# AUDIO_005.net
KiCad netlist of a schematic drawn in EAGLE
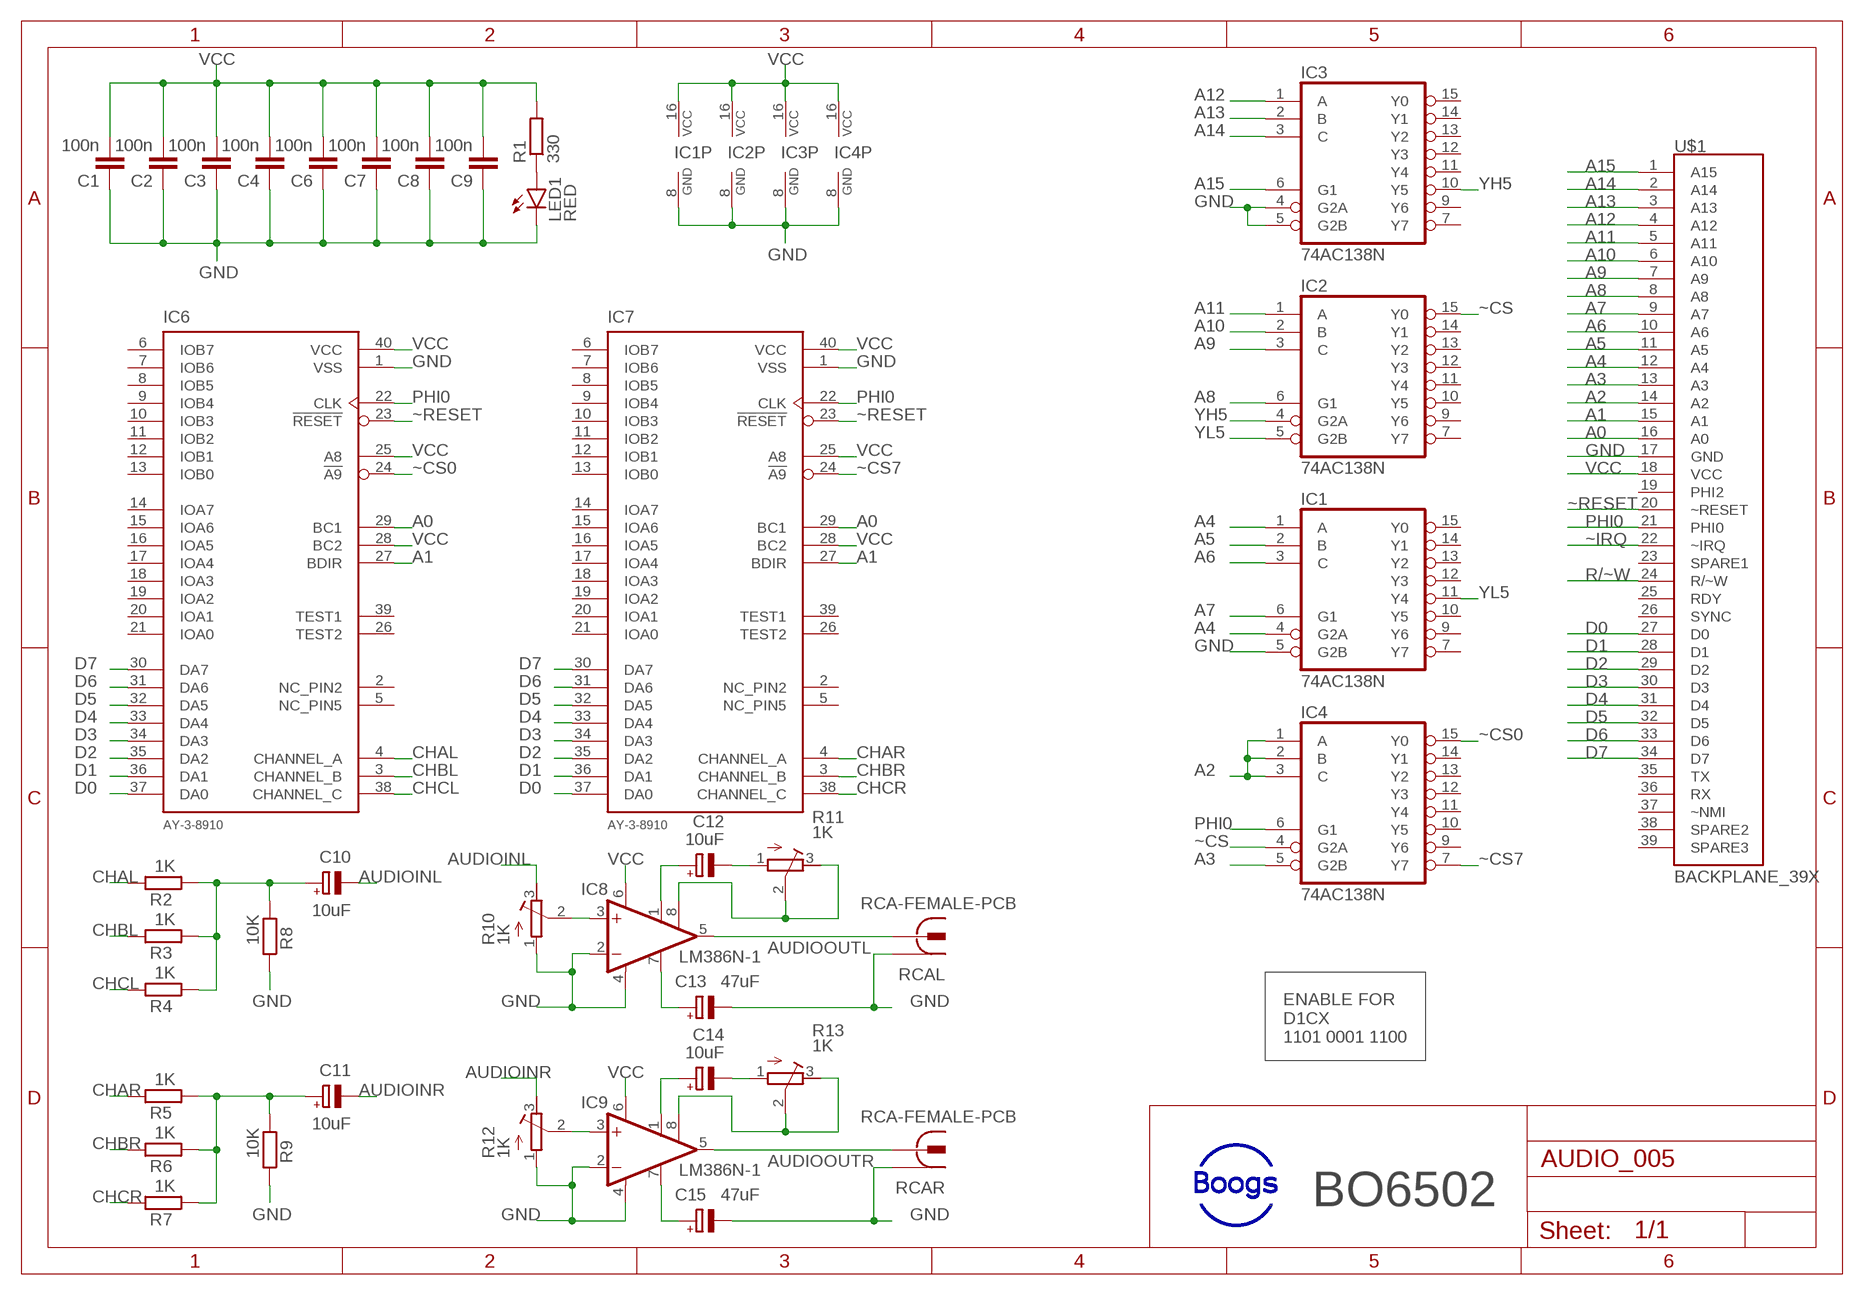
[diagram p0: schematic, sheet 1]

(export (version "E")
  (design (tool "Eeschema 10.0.6"))
  (components
    (comp (ref "C1")
      (value "100n")
      (footprint "eagle-import:C025-025X050")
      (libsource (lib "eagle-import") (part "C-EU025-025X050"))
    )
    (comp (ref "C2")
      (value "100n")
      (footprint "eagle-import:C025-025X050")
      (libsource (lib "eagle-import") (part "C-EU025-025X050"))
    )
    (comp (ref "C3")
      (value "100n")
      (footprint "eagle-import:C025-025X050")
      (libsource (lib "eagle-import") (part "C-EU025-025X050"))
    )
    (comp (ref "C4")
      (value "100n")
      (footprint "eagle-import:C025-025X050")
      (libsource (lib "eagle-import") (part "C-EU025-025X050"))
    )
    (comp (ref "C6")
      (value "100n")
      (footprint "eagle-import:C025-025X050")
      (libsource (lib "eagle-import") (part "C-EU025-025X050"))
    )
    (comp (ref "C7")
      (value "100n")
      (footprint "eagle-import:C025-025X050")
      (libsource (lib "eagle-import") (part "C-EU025-025X050"))
    )
    (comp (ref "C8")
      (value "100n")
      (footprint "eagle-import:C025-025X050")
      (libsource (lib "eagle-import") (part "C-EU025-025X050"))
    )
    (comp (ref "C9")
      (value "100n")
      (footprint "eagle-import:C025-025X050")
      (libsource (lib "eagle-import") (part "C-EU025-025X050"))
    )
    (comp (ref "C10")
      (value "10uF")
      (footprint "eagle-import:B45181A")
      (libsource (lib "eagle-import") (part "CPOL-EUB45181A"))
    )
    (comp (ref "C11")
      (value "10uF")
      (footprint "eagle-import:B45181A")
      (libsource (lib "eagle-import") (part "CPOL-EUB45181A"))
    )
    (comp (ref "C12")
      (value "10uF")
      (footprint "eagle-import:B45181A")
      (libsource (lib "eagle-import") (part "CPOL-EUB45181A"))
    )
    (comp (ref "C13")
      (value "47uF")
      (footprint "eagle-import:B45181A")
      (libsource (lib "eagle-import") (part "CPOL-EUB45181A"))
    )
    (comp (ref "C14")
      (value "10uF")
      (footprint "eagle-import:B45181A")
      (libsource (lib "eagle-import") (part "CPOL-EUB45181A"))
    )
    (comp (ref "C15")
      (value "47uF")
      (footprint "eagle-import:B45181A")
      (libsource (lib "eagle-import") (part "CPOL-EUB45181A"))
    )
    (comp (ref "IC1")
      (value "74AC138N")
      (footprint "eagle-import:DIL16")
      (libsource (lib "eagle-import") (part "74138NAC"))
    )
    (comp (ref "IC2")
      (value "74AC138N")
      (footprint "eagle-import:DIL16")
      (libsource (lib "eagle-import") (part "74138NAC"))
    )
    (comp (ref "IC3")
      (value "74AC138N")
      (footprint "eagle-import:DIL16")
      (libsource (lib "eagle-import") (part "74138NAC"))
    )
    (comp (ref "IC4")
      (value "74AC138N")
      (footprint "eagle-import:DIL16")
      (libsource (lib "eagle-import") (part "74138NAC"))
    )
    (comp (ref "IC6")
      (value "AY-3-8910")
      (footprint "eagle-import:DIL40")
      (fields (field (name "MF") "General Instrument"))
      (libsource (lib "eagle-import") (part "AY-3-8910"))
    )
    (comp (ref "IC7")
      (value "AY-3-8910")
      (footprint "eagle-import:DIL40")
      (fields (field (name "MF") "General Instrument"))
      (libsource (lib "eagle-import") (part "AY-3-8910"))
    )
    (comp (ref "IC8")
      (value "LM386N-1")
      (footprint "eagle-import:DIL08")
      (libsource (lib "eagle-import") (part "LM386?-N1"))
    )
    (comp (ref "IC9")
      (value "LM386N-1")
      (footprint "eagle-import:DIL08")
      (libsource (lib "eagle-import") (part "LM386?-N1"))
    )
    (comp (ref "LED1")
      (value "RED")
      (footprint "eagle-import:LED5MM")
      (libsource (lib "eagle-import") (part "LED5MM"))
    )
    (comp (ref "R1")
      (value "330")
      (footprint "eagle-import:0207_10")
      (libsource (lib "eagle-import") (part "R-EU_0207/10"))
    )
    (comp (ref "R2")
      (value "1K")
      (footprint "eagle-import:0207_10")
      (libsource (lib "eagle-import") (part "R-EU_0207/10"))
    )
    (comp (ref "R3")
      (value "1K")
      (footprint "eagle-import:0207_10")
      (libsource (lib "eagle-import") (part "R-EU_0207/10"))
    )
    (comp (ref "R4")
      (value "1K")
      (footprint "eagle-import:0207_10")
      (libsource (lib "eagle-import") (part "R-EU_0207/10"))
    )
    (comp (ref "R5")
      (value "1K")
      (footprint "eagle-import:0207_10")
      (libsource (lib "eagle-import") (part "R-EU_0207/10"))
    )
    (comp (ref "R6")
      (value "1K")
      (footprint "eagle-import:0207_10")
      (libsource (lib "eagle-import") (part "R-EU_0207/10"))
    )
    (comp (ref "R7")
      (value "1K")
      (footprint "eagle-import:0207_10")
      (libsource (lib "eagle-import") (part "R-EU_0207/10"))
    )
    (comp (ref "R8")
      (value "10K")
      (footprint "eagle-import:0207_10")
      (libsource (lib "eagle-import") (part "R-EU_0207/10"))
    )
    (comp (ref "R9")
      (value "10K")
      (footprint "eagle-import:0207_10")
      (libsource (lib "eagle-import") (part "R-EU_0207/10"))
    )
    (comp (ref "R10")
      (value "1K")
      (footprint "eagle-import:RTRIM3339P")
      (libsource (lib "eagle-import") (part "R-TRIMM3339P"))
    )
    (comp (ref "R11")
      (value "1K")
      (footprint "eagle-import:RTRIM3339P")
      (libsource (lib "eagle-import") (part "R-TRIMM3339P"))
    )
    (comp (ref "R12")
      (value "1K")
      (footprint "eagle-import:RTRIM3339P")
      (libsource (lib "eagle-import") (part "R-TRIMM3339P"))
    )
    (comp (ref "R13")
      (value "1K")
      (footprint "eagle-import:RTRIM3339P")
      (libsource (lib "eagle-import") (part "R-TRIMM3339P"))
    )
    (comp (ref "RCAL")
      (value "RCA-FEMALE-PCB")
      (footprint "eagle-import:RCA-FEMALE-PCB")
      (libsource (lib "eagle-import") (part "RCA-FEMALE-PCB"))
    )
    (comp (ref "RCAR")
      (value "RCA-FEMALE-PCB")
      (footprint "eagle-import:RCA-FEMALE-PCB")
      (libsource (lib "eagle-import") (part "RCA-FEMALE-PCB"))
    )
    (comp (ref "U$1")
      (value "BACKPLANE_39X")
      (footprint "eagle-import:BP_39X")
      (libsource (lib "eagle-import") (part "BACKPLANE_39X"))
    )
  )
  (nets
    (net (code "1") (name "/A0") (class "Default")
      (node (ref "IC6") (pin "29") (pinfunction "BC1_29") (pintype "input"))
      (node (ref "IC7") (pin "29") (pinfunction "BC1_29") (pintype "input"))
      (node (ref "U$1") (pin "16") (pinfunction "A0_16") (pintype "bidirectional"))
    )
    (net (code "2") (name "/A1") (class "Default")
      (node (ref "IC6") (pin "27") (pinfunction "BDIR_27") (pintype "input"))
      (node (ref "IC7") (pin "27") (pinfunction "BDIR_27") (pintype "input"))
      (node (ref "U$1") (pin "15") (pinfunction "A1_15") (pintype "bidirectional"))
    )
    (net (code "3") (name "/A2") (class "Default")
      (node (ref "IC4") (pin "1") (pinfunction "A_1") (pintype "input"))
      (node (ref "IC4") (pin "2") (pinfunction "B_2") (pintype "input"))
      (node (ref "IC4") (pin "3") (pinfunction "C_3") (pintype "input"))
      (node (ref "U$1") (pin "14") (pinfunction "A2_14") (pintype "bidirectional"))
    )
    (net (code "4") (name "/A3") (class "Default")
      (node (ref "IC4") (pin "5") (pinfunction "G2B_5") (pintype "input"))
      (node (ref "U$1") (pin "13") (pinfunction "A3_13") (pintype "bidirectional"))
    )
    (net (code "5") (name "/A4") (class "Default")
      (node (ref "IC1") (pin "1") (pinfunction "A_1") (pintype "input"))
      (node (ref "IC1") (pin "4") (pinfunction "G2A_4") (pintype "input"))
      (node (ref "U$1") (pin "12") (pinfunction "A4_12") (pintype "bidirectional"))
    )
    (net (code "6") (name "/A5") (class "Default")
      (node (ref "IC1") (pin "2") (pinfunction "B_2") (pintype "input"))
      (node (ref "U$1") (pin "11") (pinfunction "A5_11") (pintype "bidirectional"))
    )
    (net (code "7") (name "/A6") (class "Default")
      (node (ref "IC1") (pin "3") (pinfunction "C_3") (pintype "input"))
      (node (ref "U$1") (pin "10") (pinfunction "A6_10") (pintype "bidirectional"))
    )
    (net (code "8") (name "/A7") (class "Default")
      (node (ref "IC1") (pin "6") (pinfunction "G1_6") (pintype "input"))
      (node (ref "U$1") (pin "9") (pinfunction "A7_9") (pintype "bidirectional"))
    )
    (net (code "9") (name "/A8") (class "Default")
      (node (ref "IC2") (pin "6") (pinfunction "G1_6") (pintype "input"))
      (node (ref "U$1") (pin "8") (pinfunction "A8_8") (pintype "bidirectional"))
    )
    (net (code "10") (name "/A9") (class "Default")
      (node (ref "IC2") (pin "3") (pinfunction "C_3") (pintype "input"))
      (node (ref "U$1") (pin "7") (pinfunction "A9_7") (pintype "bidirectional"))
    )
    (net (code "11") (name "/A10") (class "Default")
      (node (ref "IC2") (pin "2") (pinfunction "B_2") (pintype "input"))
      (node (ref "U$1") (pin "6") (pinfunction "A10_6") (pintype "bidirectional"))
    )
    (net (code "12") (name "/A11") (class "Default")
      (node (ref "IC2") (pin "1") (pinfunction "A_1") (pintype "input"))
      (node (ref "U$1") (pin "5") (pinfunction "A11_5") (pintype "bidirectional"))
    )
    (net (code "13") (name "/A12") (class "Default")
      (node (ref "IC3") (pin "1") (pinfunction "A_1") (pintype "input"))
      (node (ref "U$1") (pin "4") (pinfunction "A12_4") (pintype "bidirectional"))
    )
    (net (code "14") (name "/A13") (class "Default")
      (node (ref "IC3") (pin "2") (pinfunction "B_2") (pintype "input"))
      (node (ref "U$1") (pin "3") (pinfunction "A13_3") (pintype "bidirectional"))
    )
    (net (code "15") (name "/A14") (class "Default")
      (node (ref "IC3") (pin "3") (pinfunction "C_3") (pintype "input"))
      (node (ref "U$1") (pin "2") (pinfunction "A14_2") (pintype "bidirectional"))
    )
    (net (code "16") (name "/A15") (class "Default")
      (node (ref "IC3") (pin "6") (pinfunction "G1_6") (pintype "input"))
      (node (ref "U$1") (pin "1") (pinfunction "A15_1") (pintype "bidirectional"))
    )
    (net (code "17") (name "/AUDIOINL") (class "Default")
      (node (ref "C10") (pin "-") (pinfunction "-_-") (pintype "passive"))
      (node (ref "R10") (pin "3") (pinfunction "E_3") (pintype "passive"))
    )
    (net (code "18") (name "/AUDIOINR") (class "Default")
      (node (ref "C11") (pin "-") (pinfunction "-_-") (pintype "passive"))
      (node (ref "R12") (pin "3") (pinfunction "E_3") (pintype "passive"))
    )
    (net (code "19") (name "/AUDIOOUTL") (class "Default")
      (node (ref "IC8") (pin "5") (pinfunction "OUT_5") (pintype "output"))
      (node (ref "RCAL") (pin "2@1") (pinfunction "2_2@1") (pintype "passive"))
      (node (ref "RCAL") (pin "2@2") (pinfunction "2_2@2") (pintype "passive"))
    )
    (net (code "20") (name "/AUDIOOUTR") (class "Default")
      (node (ref "IC9") (pin "5") (pinfunction "OUT_5") (pintype "output"))
      (node (ref "RCAR") (pin "2@1") (pinfunction "2_2@1") (pintype "passive"))
      (node (ref "RCAR") (pin "2@2") (pinfunction "2_2@2") (pintype "passive"))
    )
    (net (code "21") (name "/CHAL") (class "Default")
      (node (ref "IC6") (pin "4") (pinfunction "CHANNEL_A_4") (pintype "output"))
      (node (ref "R2") (pin "1") (pinfunction "1_1") (pintype "passive"))
    )
    (net (code "22") (name "/CHAR") (class "Default")
      (node (ref "IC7") (pin "4") (pinfunction "CHANNEL_A_4") (pintype "output"))
      (node (ref "R5") (pin "1") (pinfunction "1_1") (pintype "passive"))
    )
    (net (code "23") (name "/CHBL") (class "Default")
      (node (ref "IC6") (pin "3") (pinfunction "CHANNEL_B_3") (pintype "output"))
      (node (ref "R3") (pin "1") (pinfunction "1_1") (pintype "passive"))
    )
    (net (code "24") (name "/CHBR") (class "Default")
      (node (ref "IC7") (pin "3") (pinfunction "CHANNEL_B_3") (pintype "output"))
      (node (ref "R6") (pin "1") (pinfunction "1_1") (pintype "passive"))
    )
    (net (code "25") (name "/CHCL") (class "Default")
      (node (ref "IC6") (pin "38") (pinfunction "CHANNEL_C_38") (pintype "output"))
      (node (ref "R4") (pin "1") (pinfunction "1_1") (pintype "passive"))
    )
    (net (code "26") (name "/CHCR") (class "Default")
      (node (ref "IC7") (pin "38") (pinfunction "CHANNEL_C_38") (pintype "output"))
      (node (ref "R7") (pin "1") (pinfunction "1_1") (pintype "passive"))
    )
    (net (code "27") (name "/D0") (class "Default")
      (node (ref "IC6") (pin "37") (pinfunction "DA0_37") (pintype "bidirectional"))
      (node (ref "IC7") (pin "37") (pinfunction "DA0_37") (pintype "bidirectional"))
      (node (ref "U$1") (pin "27") (pinfunction "D0_27") (pintype "bidirectional"))
    )
    (net (code "28") (name "/D1") (class "Default")
      (node (ref "IC6") (pin "36") (pinfunction "DA1_36") (pintype "bidirectional"))
      (node (ref "IC7") (pin "36") (pinfunction "DA1_36") (pintype "bidirectional"))
      (node (ref "U$1") (pin "28") (pinfunction "D1_28") (pintype "bidirectional"))
    )
    (net (code "29") (name "/D2") (class "Default")
      (node (ref "IC6") (pin "35") (pinfunction "DA2_35") (pintype "bidirectional"))
      (node (ref "IC7") (pin "35") (pinfunction "DA2_35") (pintype "bidirectional"))
      (node (ref "U$1") (pin "29") (pinfunction "D2_29") (pintype "bidirectional"))
    )
    (net (code "30") (name "/D3") (class "Default")
      (node (ref "IC6") (pin "34") (pinfunction "DA3_34") (pintype "bidirectional"))
      (node (ref "IC7") (pin "34") (pinfunction "DA3_34") (pintype "bidirectional"))
      (node (ref "U$1") (pin "30") (pinfunction "D3_30") (pintype "bidirectional"))
    )
    (net (code "31") (name "/D4") (class "Default")
      (node (ref "IC6") (pin "33") (pinfunction "DA4_33") (pintype "bidirectional"))
      (node (ref "IC7") (pin "33") (pinfunction "DA4_33") (pintype "bidirectional"))
      (node (ref "U$1") (pin "31") (pinfunction "D4_31") (pintype "bidirectional"))
    )
    (net (code "32") (name "/D5") (class "Default")
      (node (ref "IC6") (pin "32") (pinfunction "DA5_32") (pintype "bidirectional"))
      (node (ref "IC7") (pin "32") (pinfunction "DA5_32") (pintype "bidirectional"))
      (node (ref "U$1") (pin "32") (pinfunction "D5_32") (pintype "bidirectional"))
    )
    (net (code "33") (name "/D6") (class "Default")
      (node (ref "IC6") (pin "31") (pinfunction "DA6_31") (pintype "bidirectional"))
      (node (ref "IC7") (pin "31") (pinfunction "DA6_31") (pintype "bidirectional"))
      (node (ref "U$1") (pin "33") (pinfunction "D6_33") (pintype "bidirectional"))
    )
    (net (code "34") (name "/D7") (class "Default")
      (node (ref "IC6") (pin "30") (pinfunction "DA7_30") (pintype "bidirectional"))
      (node (ref "IC7") (pin "30") (pinfunction "DA7_30") (pintype "bidirectional"))
      (node (ref "U$1") (pin "34") (pinfunction "D7_34") (pintype "bidirectional"))
    )
    (net (code "35") (name "/GND") (class "Default")
      (node (ref "C1") (pin "1") (pinfunction "1_1") (pintype "passive"))
      (node (ref "C13") (pin "-") (pinfunction "-_-") (pintype "passive"))
      (node (ref "C15") (pin "-") (pinfunction "-_-") (pintype "passive"))
      (node (ref "C2") (pin "1") (pinfunction "1_1") (pintype "passive"))
      (node (ref "C3") (pin "1") (pinfunction "1_1") (pintype "passive"))
      (node (ref "C4") (pin "1") (pinfunction "1_1") (pintype "passive"))
      (node (ref "C6") (pin "1") (pinfunction "1_1") (pintype "passive"))
      (node (ref "C7") (pin "1") (pinfunction "1_1") (pintype "passive"))
      (node (ref "C8") (pin "1") (pinfunction "1_1") (pintype "passive"))
      (node (ref "C9") (pin "1") (pinfunction "1_1") (pintype "passive"))
      (node (ref "IC1") (pin "5") (pinfunction "G2B_5") (pintype "input"))
      (node (ref "IC1") (pin "8") (pinfunction "GND_8") (pintype "power_in"))
      (node (ref "IC2") (pin "8") (pinfunction "GND_8") (pintype "power_in"))
      (node (ref "IC3") (pin "4") (pinfunction "G2A_4") (pintype "input"))
      (node (ref "IC3") (pin "5") (pinfunction "G2B_5") (pintype "input"))
      (node (ref "IC3") (pin "8") (pinfunction "GND_8") (pintype "power_in"))
      (node (ref "IC4") (pin "8") (pinfunction "GND_8") (pintype "power_in"))
      (node (ref "IC6") (pin "1") (pinfunction "VSS_1") (pintype "power_in"))
      (node (ref "IC7") (pin "1") (pinfunction "VSS_1") (pintype "power_in"))
      (node (ref "IC8") (pin "2") (pinfunction "-IN_2") (pintype "input"))
      (node (ref "IC8") (pin "4") (pinfunction "GND_4") (pintype "power_in"))
      (node (ref "IC9") (pin "2") (pinfunction "-IN_2") (pintype "input"))
      (node (ref "IC9") (pin "4") (pinfunction "GND_4") (pintype "power_in"))
      (node (ref "LED1") (pin "K") (pinfunction "C_K") (pintype "passive"))
      (node (ref "R10") (pin "1") (pinfunction "A_1") (pintype "passive"))
      (node (ref "R12") (pin "1") (pinfunction "A_1") (pintype "passive"))
      (node (ref "R8") (pin "1") (pinfunction "1_1") (pintype "passive"))
      (node (ref "R9") (pin "1") (pinfunction "1_1") (pintype "passive"))
      (node (ref "RCAL") (pin "1") (pinfunction "1_1") (pintype "passive"))
      (node (ref "RCAR") (pin "1") (pinfunction "1_1") (pintype "passive"))
      (node (ref "U$1") (pin "17") (pinfunction "GND_17") (pintype "bidirectional"))
    )
    (net (code "36") (name "/PHI0") (class "Default")
      (node (ref "IC4") (pin "6") (pinfunction "G1_6") (pintype "input"))
      (node (ref "IC6") (pin "22") (pinfunction "CLK_22") (pintype "input"))
      (node (ref "IC7") (pin "22") (pinfunction "CLK_22") (pintype "input"))
      (node (ref "U$1") (pin "21") (pinfunction "PHI0_21") (pintype "bidirectional"))
    )
    (net (code "37") (name "/R{slash}~{W}") (class "Default")
      (node (ref "U$1") (pin "24") (pinfunction "R/~{W}_24") (pintype "bidirectional"))
    )
    (net (code "38") (name "/VCC") (class "Default")
      (node (ref "C1") (pin "2") (pinfunction "2_2") (pintype "passive"))
      (node (ref "C2") (pin "2") (pinfunction "2_2") (pintype "passive"))
      (node (ref "C3") (pin "2") (pinfunction "2_2") (pintype "passive"))
      (node (ref "C4") (pin "2") (pinfunction "2_2") (pintype "passive"))
      (node (ref "C6") (pin "2") (pinfunction "2_2") (pintype "passive"))
      (node (ref "C7") (pin "2") (pinfunction "2_2") (pintype "passive"))
      (node (ref "C8") (pin "2") (pinfunction "2_2") (pintype "passive"))
      (node (ref "C9") (pin "2") (pinfunction "2_2") (pintype "passive"))
      (node (ref "IC1") (pin "16") (pinfunction "VCC_16") (pintype "power_in"))
      (node (ref "IC2") (pin "16") (pinfunction "VCC_16") (pintype "power_in"))
      (node (ref "IC3") (pin "16") (pinfunction "VCC_16") (pintype "power_in"))
      (node (ref "IC4") (pin "16") (pinfunction "VCC_16") (pintype "power_in"))
      (node (ref "IC6") (pin "25") (pinfunction "A8_25") (pintype "bidirectional"))
      (node (ref "IC6") (pin "28") (pinfunction "BC2_28") (pintype "input"))
      (node (ref "IC6") (pin "40") (pinfunction "VCC_40") (pintype "power_in"))
      (node (ref "IC7") (pin "25") (pinfunction "A8_25") (pintype "bidirectional"))
      (node (ref "IC7") (pin "28") (pinfunction "BC2_28") (pintype "input"))
      (node (ref "IC7") (pin "40") (pinfunction "VCC_40") (pintype "power_in"))
      (node (ref "IC8") (pin "6") (pinfunction "VS_6") (pintype "power_in"))
      (node (ref "IC9") (pin "6") (pinfunction "VS_6") (pintype "power_in"))
      (node (ref "R1") (pin "2") (pinfunction "2_2") (pintype "passive"))
      (node (ref "U$1") (pin "18") (pinfunction "VCC_18") (pintype "bidirectional"))
    )
    (net (code "39") (name "/YH5") (class "Default")
      (node (ref "IC2") (pin "4") (pinfunction "G2A_4") (pintype "input"))
      (node (ref "IC3") (pin "10") (pinfunction "Y5_10") (pintype "output"))
    )
    (net (code "40") (name "/YL5") (class "Default")
      (node (ref "IC1") (pin "11") (pinfunction "Y4_11") (pintype "output"))
      (node (ref "IC2") (pin "5") (pinfunction "G2B_5") (pintype "input"))
    )
    (net (code "41") (name "/~{CS0}") (class "Default")
      (node (ref "IC4") (pin "15") (pinfunction "Y0_15") (pintype "output"))
      (node (ref "IC6") (pin "24") (pinfunction "~{A9}_24") (pintype "bidirectional"))
    )
    (net (code "42") (name "/~{CS7}") (class "Default")
      (node (ref "IC4") (pin "7") (pinfunction "Y7_7") (pintype "output"))
      (node (ref "IC7") (pin "24") (pinfunction "~{A9}_24") (pintype "bidirectional"))
    )
    (net (code "43") (name "/~{CS}") (class "Default")
      (node (ref "IC2") (pin "15") (pinfunction "Y0_15") (pintype "output"))
      (node (ref "IC4") (pin "4") (pinfunction "G2A_4") (pintype "input"))
    )
    (net (code "44") (name "/~{IRQ}") (class "Default")
      (node (ref "U$1") (pin "22") (pinfunction "~{IRQ}_22") (pintype "bidirectional"))
    )
    (net (code "45") (name "/~{RESET}") (class "Default")
      (node (ref "IC6") (pin "23") (pinfunction "~{RESET}_23") (pintype "input"))
      (node (ref "IC7") (pin "23") (pinfunction "~{RESET}_23") (pintype "input"))
      (node (ref "U$1") (pin "20") (pinfunction "~{RESET}_20") (pintype "bidirectional"))
    )
    (net (code "46") (name "Net-(C10-Pad+)") (class "Default")
      (node (ref "C10") (pin "+") (pinfunction "+_+") (pintype "passive"))
      (node (ref "R2") (pin "2") (pinfunction "2_2") (pintype "passive"))
      (node (ref "R3") (pin "2") (pinfunction "2_2") (pintype "passive"))
      (node (ref "R4") (pin "2") (pinfunction "2_2") (pintype "passive"))
      (node (ref "R8") (pin "2") (pinfunction "2_2") (pintype "passive"))
    )
    (net (code "47") (name "Net-(C11-Pad+)") (class "Default")
      (node (ref "C11") (pin "+") (pinfunction "+_+") (pintype "passive"))
      (node (ref "R5") (pin "2") (pinfunction "2_2") (pintype "passive"))
      (node (ref "R6") (pin "2") (pinfunction "2_2") (pintype "passive"))
      (node (ref "R7") (pin "2") (pinfunction "2_2") (pintype "passive"))
      (node (ref "R9") (pin "2") (pinfunction "2_2") (pintype "passive"))
    )
    (net (code "48") (name "Net-(C12-Pad+)") (class "Default")
      (node (ref "C12") (pin "+") (pinfunction "+_+") (pintype "passive"))
      (node (ref "IC8") (pin "1") (pinfunction "GAIN_1") (pintype "passive"))
    )
    (net (code "49") (name "Net-(C14-Pad+)") (class "Default")
      (node (ref "C14") (pin "+") (pinfunction "+_+") (pintype "passive"))
      (node (ref "IC9") (pin "1") (pinfunction "GAIN_1") (pintype "passive"))
    )
    (net (code "50") (name "Net-(IC8-+IN)") (class "Default")
      (node (ref "IC8") (pin "3") (pinfunction "+IN_3") (pintype "input"))
      (node (ref "R10") (pin "2") (pinfunction "S_2") (pintype "passive"))
    )
    (net (code "51") (name "Net-(IC8-BYPASS)") (class "Default")
      (node (ref "C13") (pin "+") (pinfunction "+_+") (pintype "passive"))
      (node (ref "IC8") (pin "7") (pinfunction "BYPASS_7") (pintype "passive"))
    )
    (net (code "52") (name "Net-(IC9-+IN)") (class "Default")
      (node (ref "IC9") (pin "3") (pinfunction "+IN_3") (pintype "input"))
      (node (ref "R12") (pin "2") (pinfunction "S_2") (pintype "passive"))
    )
    (net (code "53") (name "Net-(IC9-BYPASS)") (class "Default")
      (node (ref "C15") (pin "+") (pinfunction "+_+") (pintype "passive"))
      (node (ref "IC9") (pin "7") (pinfunction "BYPASS_7") (pintype "passive"))
    )
    (net (code "54") (name "Net-(LED1-PadA)") (class "Default")
      (node (ref "LED1") (pin "A") (pinfunction "A_A") (pintype "passive"))
      (node (ref "R1") (pin "1") (pinfunction "1_1") (pintype "passive"))
    )
    (net (code "55") (name "Net-(R11-A)") (class "Default")
      (node (ref "C12") (pin "-") (pinfunction "-_-") (pintype "passive"))
      (node (ref "R11") (pin "1") (pinfunction "A_1") (pintype "passive"))
    )
    (net (code "56") (name "Net-(R11-E)") (class "Default")
      (node (ref "IC8") (pin "8") (pinfunction "GAIN_8") (pintype "passive"))
      (node (ref "R11") (pin "2") (pinfunction "S_2") (pintype "passive"))
      (node (ref "R11") (pin "3") (pinfunction "E_3") (pintype "passive"))
    )
    (net (code "57") (name "Net-(R13-A)") (class "Default")
      (node (ref "C14") (pin "-") (pinfunction "-_-") (pintype "passive"))
      (node (ref "R13") (pin "1") (pinfunction "A_1") (pintype "passive"))
    )
    (net (code "58") (name "Net-(R13-E)") (class "Default")
      (node (ref "IC9") (pin "8") (pinfunction "GAIN_8") (pintype "passive"))
      (node (ref "R13") (pin "2") (pinfunction "S_2") (pintype "passive"))
      (node (ref "R13") (pin "3") (pinfunction "E_3") (pintype "passive"))
    )
    (net (code "59") (name "unconnected-(IC1A-Y0-Pad15)") (class "Default")
      (node (ref "IC1") (pin "15") (pinfunction "Y0_15") (pintype "output"))
    )
    (net (code "60") (name "unconnected-(IC1A-Y1-Pad14)") (class "Default")
      (node (ref "IC1") (pin "14") (pinfunction "Y1_14") (pintype "output"))
    )
    (net (code "61") (name "unconnected-(IC1A-Y2-Pad13)") (class "Default")
      (node (ref "IC1") (pin "13") (pinfunction "Y2_13") (pintype "output"))
    )
    (net (code "62") (name "unconnected-(IC1A-Y3-Pad12)") (class "Default")
      (node (ref "IC1") (pin "12") (pinfunction "Y3_12") (pintype "output"))
    )
    (net (code "63") (name "unconnected-(IC1A-Y5-Pad10)") (class "Default")
      (node (ref "IC1") (pin "10") (pinfunction "Y5_10") (pintype "output"))
    )
    (net (code "64") (name "unconnected-(IC1A-Y6-Pad9)") (class "Default")
      (node (ref "IC1") (pin "9") (pinfunction "Y6_9") (pintype "output"))
    )
    (net (code "65") (name "unconnected-(IC1A-Y7-Pad7)") (class "Default")
      (node (ref "IC1") (pin "7") (pinfunction "Y7_7") (pintype "output"))
    )
    (net (code "66") (name "unconnected-(IC2A-Y1-Pad14)") (class "Default")
      (node (ref "IC2") (pin "14") (pinfunction "Y1_14") (pintype "output"))
    )
    (net (code "67") (name "unconnected-(IC2A-Y2-Pad13)") (class "Default")
      (node (ref "IC2") (pin "13") (pinfunction "Y2_13") (pintype "output"))
    )
    (net (code "68") (name "unconnected-(IC2A-Y3-Pad12)") (class "Default")
      (node (ref "IC2") (pin "12") (pinfunction "Y3_12") (pintype "output"))
    )
    (net (code "69") (name "unconnected-(IC2A-Y4-Pad11)") (class "Default")
      (node (ref "IC2") (pin "11") (pinfunction "Y4_11") (pintype "output"))
    )
    (net (code "70") (name "unconnected-(IC2A-Y5-Pad10)") (class "Default")
      (node (ref "IC2") (pin "10") (pinfunction "Y5_10") (pintype "output"))
    )
    (net (code "71") (name "unconnected-(IC2A-Y6-Pad9)") (class "Default")
      (node (ref "IC2") (pin "9") (pinfunction "Y6_9") (pintype "output"))
    )
    (net (code "72") (name "unconnected-(IC2A-Y7-Pad7)") (class "Default")
      (node (ref "IC2") (pin "7") (pinfunction "Y7_7") (pintype "output"))
    )
    (net (code "73") (name "unconnected-(IC3A-Y0-Pad15)") (class "Default")
      (node (ref "IC3") (pin "15") (pinfunction "Y0_15") (pintype "output"))
    )
    (net (code "74") (name "unconnected-(IC3A-Y1-Pad14)") (class "Default")
      (node (ref "IC3") (pin "14") (pinfunction "Y1_14") (pintype "output"))
    )
    (net (code "75") (name "unconnected-(IC3A-Y2-Pad13)") (class "Default")
      (node (ref "IC3") (pin "13") (pinfunction "Y2_13") (pintype "output"))
    )
    (net (code "76") (name "unconnected-(IC3A-Y3-Pad12)") (class "Default")
      (node (ref "IC3") (pin "12") (pinfunction "Y3_12") (pintype "output"))
    )
    (net (code "77") (name "unconnected-(IC3A-Y4-Pad11)") (class "Default")
      (node (ref "IC3") (pin "11") (pinfunction "Y4_11") (pintype "output"))
    )
    (net (code "78") (name "unconnected-(IC3A-Y6-Pad9)") (class "Default")
      (node (ref "IC3") (pin "9") (pinfunction "Y6_9") (pintype "output"))
    )
    (net (code "79") (name "unconnected-(IC3A-Y7-Pad7)") (class "Default")
      (node (ref "IC3") (pin "7") (pinfunction "Y7_7") (pintype "output"))
    )
    (net (code "80") (name "unconnected-(IC4A-Y1-Pad14)") (class "Default")
      (node (ref "IC4") (pin "14") (pinfunction "Y1_14") (pintype "output"))
    )
    (net (code "81") (name "unconnected-(IC4A-Y2-Pad13)") (class "Default")
      (node (ref "IC4") (pin "13") (pinfunction "Y2_13") (pintype "output"))
    )
    (net (code "82") (name "unconnected-(IC4A-Y3-Pad12)") (class "Default")
      (node (ref "IC4") (pin "12") (pinfunction "Y3_12") (pintype "output"))
    )
    (net (code "83") (name "unconnected-(IC4A-Y4-Pad11)") (class "Default")
      (node (ref "IC4") (pin "11") (pinfunction "Y4_11") (pintype "output"))
    )
    (net (code "84") (name "unconnected-(IC4A-Y5-Pad10)") (class "Default")
      (node (ref "IC4") (pin "10") (pinfunction "Y5_10") (pintype "output"))
    )
    (net (code "85") (name "unconnected-(IC4A-Y6-Pad9)") (class "Default")
      (node (ref "IC4") (pin "9") (pinfunction "Y6_9") (pintype "output"))
    )
    (net (code "86") (name "unconnected-(IC6-IOA0-Pad21)") (class "Default")
      (node (ref "IC6") (pin "21") (pinfunction "IOA0_21") (pintype "bidirectional"))
    )
    (net (code "87") (name "unconnected-(IC6-IOA1-Pad20)") (class "Default")
      (node (ref "IC6") (pin "20") (pinfunction "IOA1_20") (pintype "bidirectional"))
    )
    (net (code "88") (name "unconnected-(IC6-IOA2-Pad19)") (class "Default")
      (node (ref "IC6") (pin "19") (pinfunction "IOA2_19") (pintype "bidirectional"))
    )
    (net (code "89") (name "unconnected-(IC6-IOA3-Pad18)") (class "Default")
      (node (ref "IC6") (pin "18") (pinfunction "IOA3_18") (pintype "bidirectional"))
    )
    (net (code "90") (name "unconnected-(IC6-IOA4-Pad17)") (class "Default")
      (node (ref "IC6") (pin "17") (pinfunction "IOA4_17") (pintype "bidirectional"))
    )
    (net (code "91") (name "unconnected-(IC6-IOA5-Pad16)") (class "Default")
      (node (ref "IC6") (pin "16") (pinfunction "IOA5_16") (pintype "bidirectional"))
    )
    (net (code "92") (name "unconnected-(IC6-IOA6-Pad15)") (class "Default")
      (node (ref "IC6") (pin "15") (pinfunction "IOA6_15") (pintype "bidirectional"))
    )
    (net (code "93") (name "unconnected-(IC6-IOA7-Pad14)") (class "Default")
      (node (ref "IC6") (pin "14") (pinfunction "IOA7_14") (pintype "bidirectional"))
    )
    (net (code "94") (name "unconnected-(IC6-IOB0-Pad13)") (class "Default")
      (node (ref "IC6") (pin "13") (pinfunction "IOB0_13") (pintype "bidirectional"))
    )
    (net (code "95") (name "unconnected-(IC6-IOB1-Pad12)") (class "Default")
      (node (ref "IC6") (pin "12") (pinfunction "IOB1_12") (pintype "bidirectional"))
    )
    (net (code "96") (name "unconnected-(IC6-IOB2-Pad11)") (class "Default")
      (node (ref "IC6") (pin "11") (pinfunction "IOB2_11") (pintype "bidirectional"))
    )
    (net (code "97") (name "unconnected-(IC6-IOB3-Pad10)") (class "Default")
      (node (ref "IC6") (pin "10") (pinfunction "IOB3_10") (pintype "bidirectional"))
    )
    (net (code "98") (name "unconnected-(IC6-IOB4-Pad9)") (class "Default")
      (node (ref "IC6") (pin "9") (pinfunction "IOB4_9") (pintype "bidirectional"))
    )
    (net (code "99") (name "unconnected-(IC6-IOB5-Pad8)") (class "Default")
      (node (ref "IC6") (pin "8") (pinfunction "IOB5_8") (pintype "bidirectional"))
    )
    (net (code "100") (name "unconnected-(IC6-IOB6-Pad7)") (class "Default")
      (node (ref "IC6") (pin "7") (pinfunction "IOB6_7") (pintype "bidirectional"))
    )
    (net (code "101") (name "unconnected-(IC6-IOB7-Pad6)") (class "Default")
      (node (ref "IC6") (pin "6") (pinfunction "IOB7_6") (pintype "bidirectional"))
    )
    (net (code "102") (name "unconnected-(IC6-NC_PIN2-Pad2)") (class "Default")
      (node (ref "IC6") (pin "2") (pinfunction "NC_PIN2_2") (pintype "no_connect"))
    )
    (net (code "103") (name "unconnected-(IC6-NC_PIN5-Pad5)") (class "Default")
      (node (ref "IC6") (pin "5") (pinfunction "NC_PIN5_5") (pintype "bidirectional"))
    )
    (net (code "104") (name "unconnected-(IC6-TEST1-Pad39)") (class "Default")
      (node (ref "IC6") (pin "39") (pinfunction "TEST1_39") (pintype "no_connect"))
    )
    (net (code "105") (name "unconnected-(IC6-TEST2-Pad26)") (class "Default")
      (node (ref "IC6") (pin "26") (pinfunction "TEST2_26") (pintype "no_connect"))
    )
    (net (code "106") (name "unconnected-(IC7-IOA0-Pad21)") (class "Default")
      (node (ref "IC7") (pin "21") (pinfunction "IOA0_21") (pintype "bidirectional"))
    )
    (net (code "107") (name "unconnected-(IC7-IOA1-Pad20)") (class "Default")
      (node (ref "IC7") (pin "20") (pinfunction "IOA1_20") (pintype "bidirectional"))
    )
    (net (code "108") (name "unconnected-(IC7-IOA2-Pad19)") (class "Default")
      (node (ref "IC7") (pin "19") (pinfunction "IOA2_19") (pintype "bidirectional"))
    )
    (net (code "109") (name "unconnected-(IC7-IOA3-Pad18)") (class "Default")
      (node (ref "IC7") (pin "18") (pinfunction "IOA3_18") (pintype "bidirectional"))
    )
    (net (code "110") (name "unconnected-(IC7-IOA4-Pad17)") (class "Default")
      (node (ref "IC7") (pin "17") (pinfunction "IOA4_17") (pintype "bidirectional"))
    )
    (net (code "111") (name "unconnected-(IC7-IOA5-Pad16)") (class "Default")
      (node (ref "IC7") (pin "16") (pinfunction "IOA5_16") (pintype "bidirectional"))
    )
    (net (code "112") (name "unconnected-(IC7-IOA6-Pad15)") (class "Default")
      (node (ref "IC7") (pin "15") (pinfunction "IOA6_15") (pintype "bidirectional"))
    )
    (net (code "113") (name "unconnected-(IC7-IOA7-Pad14)") (class "Default")
      (node (ref "IC7") (pin "14") (pinfunction "IOA7_14") (pintype "bidirectional"))
    )
    (net (code "114") (name "unconnected-(IC7-IOB0-Pad13)") (class "Default")
      (node (ref "IC7") (pin "13") (pinfunction "IOB0_13") (pintype "bidirectional"))
    )
    (net (code "115") (name "unconnected-(IC7-IOB1-Pad12)") (class "Default")
      (node (ref "IC7") (pin "12") (pinfunction "IOB1_12") (pintype "bidirectional"))
    )
    (net (code "116") (name "unconnected-(IC7-IOB2-Pad11)") (class "Default")
      (node (ref "IC7") (pin "11") (pinfunction "IOB2_11") (pintype "bidirectional"))
    )
    (net (code "117") (name "unconnected-(IC7-IOB3-Pad10)") (class "Default")
      (node (ref "IC7") (pin "10") (pinfunction "IOB3_10") (pintype "bidirectional"))
    )
    (net (code "118") (name "unconnected-(IC7-IOB4-Pad9)") (class "Default")
      (node (ref "IC7") (pin "9") (pinfunction "IOB4_9") (pintype "bidirectional"))
    )
    (net (code "119") (name "unconnected-(IC7-IOB5-Pad8)") (class "Default")
      (node (ref "IC7") (pin "8") (pinfunction "IOB5_8") (pintype "bidirectional"))
    )
    (net (code "120") (name "unconnected-(IC7-IOB6-Pad7)") (class "Default")
      (node (ref "IC7") (pin "7") (pinfunction "IOB6_7") (pintype "bidirectional"))
    )
    (net (code "121") (name "unconnected-(IC7-IOB7-Pad6)") (class "Default")
      (node (ref "IC7") (pin "6") (pinfunction "IOB7_6") (pintype "bidirectional"))
    )
    (net (code "122") (name "unconnected-(IC7-NC_PIN2-Pad2)") (class "Default")
      (node (ref "IC7") (pin "2") (pinfunction "NC_PIN2_2") (pintype "no_connect"))
    )
    (net (code "123") (name "unconnected-(IC7-NC_PIN5-Pad5)") (class "Default")
      (node (ref "IC7") (pin "5") (pinfunction "NC_PIN5_5") (pintype "bidirectional"))
    )
    (net (code "124") (name "unconnected-(IC7-TEST1-Pad39)") (class "Default")
      (node (ref "IC7") (pin "39") (pinfunction "TEST1_39") (pintype "no_connect"))
    )
    (net (code "125") (name "unconnected-(IC7-TEST2-Pad26)") (class "Default")
      (node (ref "IC7") (pin "26") (pinfunction "TEST2_26") (pintype "no_connect"))
    )
    (net (code "126") (name "unconnected-(U$1-PHI2-Pad19)") (class "Default")
      (node (ref "U$1") (pin "19") (pinfunction "PHI2_19") (pintype "bidirectional"))
    )
    (net (code "127") (name "unconnected-(U$1-RDY-Pad25)") (class "Default")
      (node (ref "U$1") (pin "25") (pinfunction "RDY_25") (pintype "bidirectional"))
    )
    (net (code "128") (name "unconnected-(U$1-RX-Pad36)") (class "Default")
      (node (ref "U$1") (pin "36") (pinfunction "RX_36") (pintype "bidirectional"))
    )
    (net (code "129") (name "unconnected-(U$1-SPARE1-Pad23)") (class "Default")
      (node (ref "U$1") (pin "23") (pinfunction "SPARE1_23") (pintype "bidirectional"))
    )
    (net (code "130") (name "unconnected-(U$1-SPARE2-Pad38)") (class "Default")
      (node (ref "U$1") (pin "38") (pinfunction "SPARE2_38") (pintype "bidirectional"))
    )
    (net (code "131") (name "unconnected-(U$1-SPARE3-Pad39)") (class "Default")
      (node (ref "U$1") (pin "39") (pinfunction "SPARE3_39") (pintype "bidirectional"))
    )
    (net (code "132") (name "unconnected-(U$1-SYNC-Pad26)") (class "Default")
      (node (ref "U$1") (pin "26") (pinfunction "SYNC_26") (pintype "bidirectional"))
    )
    (net (code "133") (name "unconnected-(U$1-TX-Pad35)") (class "Default")
      (node (ref "U$1") (pin "35") (pinfunction "TX_35") (pintype "bidirectional"))
    )
    (net (code "134") (name "unconnected-(U$1-~{NMI}-Pad37)") (class "Default")
      (node (ref "U$1") (pin "37") (pinfunction "~{NMI}_37") (pintype "bidirectional"))
    )
  )
)
